# QCopterFC_MCU_Sch.net
KiCad netlist of a schematic drawn in Altium Designer
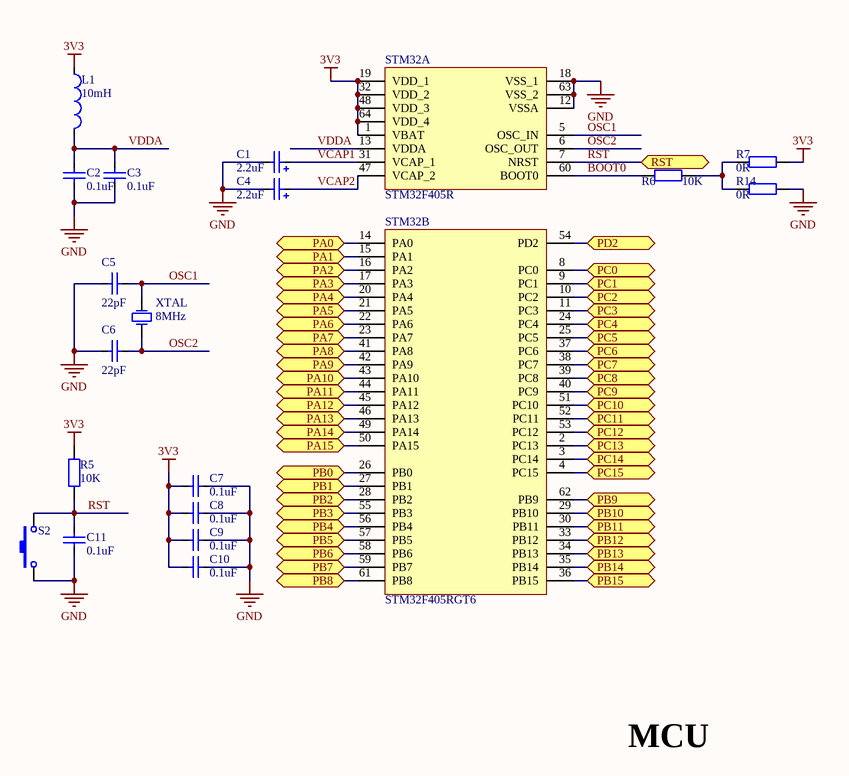
[diagram p0: QCopterFC_MCU_Sch.SchDoc]

(export (version "E")
  (design (tool "Eeschema 10.0.6"))
  (components
    (comp (ref "C1")
      (value "2.2uF")
      (footprint "PCB_Passive:CAP_TAN_P0805")
      (description "Capacitor")
      (fields (field (name "Comment") "Cap_Tan_0805"))
      (libsource (lib "SCH_Passive") (part "Cap_Tan_0805"))
    )
    (comp (ref "C2")
      (value "0.1uF")
      (footprint "PCB_Passive:CAP_0603")
      (description "Capacitor")
      (fields (field (name "Comment") "Cap_0603"))
      (libsource (lib "SCH_Passive") (part "Cap_0603"))
    )
    (comp (ref "C3")
      (value "0.1uF")
      (footprint "PCB_Passive:CAP_0603")
      (description "Capacitor")
      (fields (field (name "Comment") "Cap_0603"))
      (libsource (lib "SCH_Passive") (part "Cap_0603"))
    )
    (comp (ref "C4")
      (value "2.2uF")
      (footprint "PCB_Passive:CAP_TAN_P0805")
      (description "Capacitor")
      (fields (field (name "Comment") "Cap_Tan_0805"))
      (libsource (lib "SCH_Passive") (part "Cap_Tan_0805"))
    )
    (comp (ref "C5")
      (value "22pF")
      (footprint "PCB_Passive:CAP_0603")
      (description "Capacitor")
      (fields (field (name "Comment") "Cap_0603"))
      (libsource (lib "SCH_Passive") (part "Cap_0603"))
    )
    (comp (ref "C6")
      (value "22pF")
      (footprint "PCB_Passive:CAP_0603")
      (description "Capacitor")
      (fields (field (name "Comment") "Cap_0603"))
      (libsource (lib "SCH_Passive") (part "Cap_0603"))
    )
    (comp (ref "C7")
      (value "0.1uF")
      (footprint "PCB_Passive:CAP_0603")
      (description "Capacitor")
      (fields (field (name "Comment") "Cap_0603"))
      (libsource (lib "SCH_Passive") (part "Cap_0603"))
    )
    (comp (ref "C8")
      (value "0.1uF")
      (footprint "PCB_Passive:CAP_0603")
      (description "Capacitor")
      (fields (field (name "Comment") "Cap_0603"))
      (libsource (lib "SCH_Passive") (part "Cap_0603"))
    )
    (comp (ref "C9")
      (value "0.1uF")
      (footprint "PCB_Passive:CAP_0603")
      (description "Capacitor")
      (fields (field (name "Comment") "Cap_0603"))
      (libsource (lib "SCH_Passive") (part "Cap_0603"))
    )
    (comp (ref "C10")
      (value "0.1uF")
      (footprint "PCB_Passive:CAP_0603")
      (description "Capacitor")
      (fields (field (name "Comment") "Cap_0603"))
      (libsource (lib "SCH_Passive") (part "Cap_0603"))
    )
    (comp (ref "C11")
      (value "0.1uF")
      (footprint "PCB_Passive:CAP_0603")
      (description "Capacitor")
      (fields (field (name "Comment") "Cap_0603"))
      (libsource (lib "SCH_Passive") (part "Cap_0603"))
    )
    (comp (ref "L1")
      (value "10mH")
      (footprint "PCB_Passive:IND_0603")
      (description "Inductor")
      (fields (field (name "Comment") "Ind_0603"))
      (libsource (lib "SCH_Passive") (part "Ind_0603"))
    )
    (comp (ref "R5")
      (value "10K")
      (footprint "PCB_Passive:RES_0603")
      (description "Resistor")
      (fields (field (name "Comment") "Res_0603"))
      (libsource (lib "") (part "Res_0603_1"))
    )
    (comp (ref "R6")
      (value "10K")
      (footprint "PCB_Passive:RES_0603")
      (description "Resistor")
      (fields (field (name "Comment") "Res_0603"))
      (libsource (lib "SCH_Passive") (part "Res_0603"))
    )
    (comp (ref "R7")
      (value "0R")
      (footprint "PCB_Passive:RES_0603")
      (description "Resistor")
      (fields (field (name "Comment") "Res_0603"))
      (libsource (lib "SCH_Passive") (part "Res_0603"))
    )
    (comp (ref "R14")
      (value "0R")
      (footprint "PCB_Passive:RES_0603")
      (description "Resistor")
      (fields (field (name "Comment") "Res_0603"))
      (libsource (lib "SCH_Passive") (part "Res_0603"))
    )
    (comp (ref "S2")
      (value "SW-PB_1")
      (footprint "PCB_Switch:BT_90_T")
      (description "Switch")
      (fields (field (name "PUBLISHER") "Altium Limited"))
      (libsource (lib "SCH_Switch") (part "SW-PB_1"))
    )
    (comp (ref "STM32")
      (value "STM32F405R")
      (footprint "PCB_IC:STM32F_64")
      (description "MCU")
      (libsource (lib "SCH_IC") (part "STM32F405R"))
    )
    (comp (ref "XTAL")
      (value "8MHz")
      (footprint "PCB_Oscillator:XTAL_5032")
      (description "Crystal Oscillator")
      (fields (field (name "Comment") "XTAL_5032") (field (name "PUBLISHER") "Altium Limited"))
      (libsource (lib "SCH_Oscillator") (part "XTAL_5032"))
    )
  )
  (nets
    (net (code "1") (name "/BOOT0") (class "Default")
      (node (ref "R6") (pin "1") (pinfunction "1_1") (pintype "passive"))
      (node (ref "STM32") (pin "60") (pinfunction "BOOT0_60") (pintype "passive"))
    )
    (net (code "2") (name "/OSC1") (class "Default")
      (node (ref "C5") (pin "2") (pinfunction "2_2") (pintype "passive"))
      (node (ref "STM32") (pin "5") (pinfunction "OSC_IN_5") (pintype "passive"))
      (node (ref "XTAL") (pin "2") (pinfunction "OSC2_2") (pintype "passive"))
    )
    (net (code "3") (name "/OSC2") (class "Default")
      (node (ref "C6") (pin "2") (pinfunction "2_2") (pintype "passive"))
      (node (ref "STM32") (pin "6") (pinfunction "OSC_OUT_6") (pintype "passive"))
      (node (ref "XTAL") (pin "1") (pinfunction "OSC1_1") (pintype "passive"))
    )
    (net (code "4") (name "/PA0") (class "Default")
      (node (ref "STM32") (pin "14") (pinfunction "PA0_14") (pintype "passive"))
    )
    (net (code "5") (name "/PA1") (class "Default")
      (node (ref "STM32") (pin "15") (pinfunction "PA1_15") (pintype "passive"))
    )
    (net (code "6") (name "/PA2") (class "Default")
      (node (ref "STM32") (pin "16") (pinfunction "PA2_16") (pintype "passive"))
    )
    (net (code "7") (name "/PA3") (class "Default")
      (node (ref "STM32") (pin "17") (pinfunction "PA3_17") (pintype "passive"))
    )
    (net (code "8") (name "/PA4") (class "Default")
      (node (ref "STM32") (pin "20") (pinfunction "PA4_20") (pintype "passive"))
    )
    (net (code "9") (name "/PA5") (class "Default")
      (node (ref "STM32") (pin "21") (pinfunction "PA5_21") (pintype "passive"))
    )
    (net (code "10") (name "/PA6") (class "Default")
      (node (ref "STM32") (pin "22") (pinfunction "PA6_22") (pintype "passive"))
    )
    (net (code "11") (name "/PA7") (class "Default")
      (node (ref "STM32") (pin "23") (pinfunction "PA7_23") (pintype "passive"))
    )
    (net (code "12") (name "/PA8") (class "Default")
      (node (ref "STM32") (pin "41") (pinfunction "PA8_41") (pintype "passive"))
    )
    (net (code "13") (name "/PA9") (class "Default")
      (node (ref "STM32") (pin "42") (pinfunction "PA9_42") (pintype "passive"))
    )
    (net (code "14") (name "/PA10") (class "Default")
      (node (ref "STM32") (pin "43") (pinfunction "PA10_43") (pintype "passive"))
    )
    (net (code "15") (name "/PA11") (class "Default")
      (node (ref "STM32") (pin "44") (pinfunction "PA11_44") (pintype "passive"))
    )
    (net (code "16") (name "/PA12") (class "Default")
      (node (ref "STM32") (pin "45") (pinfunction "PA12_45") (pintype "passive"))
    )
    (net (code "17") (name "/PA13") (class "Default")
      (node (ref "STM32") (pin "46") (pinfunction "PA13_46") (pintype "passive"))
    )
    (net (code "18") (name "/PA14") (class "Default")
      (node (ref "STM32") (pin "49") (pinfunction "PA14_49") (pintype "passive"))
    )
    (net (code "19") (name "/PA15") (class "Default")
      (node (ref "STM32") (pin "50") (pinfunction "PA15_50") (pintype "passive"))
    )
    (net (code "20") (name "/PB0") (class "Default")
      (node (ref "STM32") (pin "26") (pinfunction "PB0_26") (pintype "passive"))
    )
    (net (code "21") (name "/PB1") (class "Default")
      (node (ref "STM32") (pin "27") (pinfunction "PB1_27") (pintype "passive"))
    )
    (net (code "22") (name "/PB2") (class "Default")
      (node (ref "STM32") (pin "28") (pinfunction "PB2_28") (pintype "passive"))
    )
    (net (code "23") (name "/PB3") (class "Default")
      (node (ref "STM32") (pin "55") (pinfunction "PB3_55") (pintype "passive"))
    )
    (net (code "24") (name "/PB4") (class "Default")
      (node (ref "STM32") (pin "56") (pinfunction "PB4_56") (pintype "passive"))
    )
    (net (code "25") (name "/PB5") (class "Default")
      (node (ref "STM32") (pin "57") (pinfunction "PB5_57") (pintype "passive"))
    )
    (net (code "26") (name "/PB6") (class "Default")
      (node (ref "STM32") (pin "58") (pinfunction "PB6_58") (pintype "passive"))
    )
    (net (code "27") (name "/PB7") (class "Default")
      (node (ref "STM32") (pin "59") (pinfunction "PB7_59") (pintype "passive"))
    )
    (net (code "28") (name "/PB8") (class "Default")
      (node (ref "STM32") (pin "61") (pinfunction "PB8_61") (pintype "passive"))
    )
    (net (code "29") (name "/PB9") (class "Default")
      (node (ref "STM32") (pin "62") (pinfunction "PB9_62") (pintype "passive"))
    )
    (net (code "30") (name "/PB10") (class "Default")
      (node (ref "STM32") (pin "29") (pinfunction "PB10_29") (pintype "passive"))
    )
    (net (code "31") (name "/PB11") (class "Default")
      (node (ref "STM32") (pin "30") (pinfunction "PB11_30") (pintype "passive"))
    )
    (net (code "32") (name "/PB12") (class "Default")
      (node (ref "STM32") (pin "33") (pinfunction "PB12_33") (pintype "passive"))
    )
    (net (code "33") (name "/PB13") (class "Default")
      (node (ref "STM32") (pin "34") (pinfunction "PB13_34") (pintype "passive"))
    )
    (net (code "34") (name "/PB14") (class "Default")
      (node (ref "STM32") (pin "35") (pinfunction "PB14_35") (pintype "passive"))
    )
    (net (code "35") (name "/PB15") (class "Default")
      (node (ref "STM32") (pin "36") (pinfunction "PB15_36") (pintype "passive"))
    )
    (net (code "36") (name "/PC0") (class "Default")
      (node (ref "STM32") (pin "8") (pinfunction "PC0_8") (pintype "passive"))
    )
    (net (code "37") (name "/PC1") (class "Default")
      (node (ref "STM32") (pin "9") (pinfunction "PC1_9") (pintype "passive"))
    )
    (net (code "38") (name "/PC2") (class "Default")
      (node (ref "STM32") (pin "10") (pinfunction "PC2_10") (pintype "passive"))
    )
    (net (code "39") (name "/PC3") (class "Default")
      (node (ref "STM32") (pin "11") (pinfunction "PC3_11") (pintype "passive"))
    )
    (net (code "40") (name "/PC4") (class "Default")
      (node (ref "STM32") (pin "24") (pinfunction "PC4_24") (pintype "passive"))
    )
    (net (code "41") (name "/PC5") (class "Default")
      (node (ref "STM32") (pin "25") (pinfunction "PC5_25") (pintype "passive"))
    )
    (net (code "42") (name "/PC6") (class "Default")
      (node (ref "STM32") (pin "37") (pinfunction "PC6_37") (pintype "passive"))
    )
    (net (code "43") (name "/PC7") (class "Default")
      (node (ref "STM32") (pin "38") (pinfunction "PC7_38") (pintype "passive"))
    )
    (net (code "44") (name "/PC8") (class "Default")
      (node (ref "STM32") (pin "39") (pinfunction "PC8_39") (pintype "passive"))
    )
    (net (code "45") (name "/PC9") (class "Default")
      (node (ref "STM32") (pin "40") (pinfunction "PC9_40") (pintype "passive"))
    )
    (net (code "46") (name "/PC10") (class "Default")
      (node (ref "STM32") (pin "51") (pinfunction "PC10_51") (pintype "passive"))
    )
    (net (code "47") (name "/PC11") (class "Default")
      (node (ref "STM32") (pin "52") (pinfunction "PC11_52") (pintype "passive"))
    )
    (net (code "48") (name "/PC12") (class "Default")
      (node (ref "STM32") (pin "53") (pinfunction "PC12_53") (pintype "passive"))
    )
    (net (code "49") (name "/PC13") (class "Default")
      (node (ref "STM32") (pin "2") (pinfunction "PC13_2") (pintype "passive"))
    )
    (net (code "50") (name "/PC14") (class "Default")
      (node (ref "STM32") (pin "3") (pinfunction "PC14_3") (pintype "passive"))
    )
    (net (code "51") (name "/PC15") (class "Default")
      (node (ref "STM32") (pin "4") (pinfunction "PC15_4") (pintype "passive"))
    )
    (net (code "52") (name "/PD2") (class "Default")
      (node (ref "STM32") (pin "54") (pinfunction "PD2_54") (pintype "passive"))
    )
    (net (code "53") (name "/RST") (class "Default")
      (node (ref "C11") (pin "1") (pinfunction "1_1") (pintype "passive"))
      (node (ref "R5") (pin "2") (pinfunction "2_2") (pintype "passive"))
      (node (ref "S2") (pin "2") (pinfunction "2_2") (pintype "passive"))
      (node (ref "STM32") (pin "7") (pinfunction "NRST_7") (pintype "passive"))
    )
    (net (code "54") (name "/VCAP1") (class "Default")
      (node (ref "C1") (pin "1") (pinfunction "1_1") (pintype "passive"))
      (node (ref "STM32") (pin "31") (pinfunction "VCAP_1_31") (pintype "passive"))
    )
    (net (code "55") (name "/VCAP2") (class "Default")
      (node (ref "C4") (pin "1") (pinfunction "1_1") (pintype "passive"))
      (node (ref "STM32") (pin "47") (pinfunction "VCAP_2_47") (pintype "passive"))
    )
    (net (code "56") (name "/VDDA") (class "Default")
      (node (ref "C2") (pin "1") (pinfunction "1_1") (pintype "passive"))
      (node (ref "C3") (pin "1") (pinfunction "1_1") (pintype "passive"))
      (node (ref "L1") (pin "2") (pinfunction "2_2") (pintype "passive"))
      (node (ref "STM32") (pin "13") (pinfunction "VDDA_13") (pintype "passive"))
    )
    (net (code "57") (name "3V3") (class "Default")
      (node (ref "C10") (pin "2") (pinfunction "2_2") (pintype "passive"))
      (node (ref "C7") (pin "2") (pinfunction "2_2") (pintype "passive"))
      (node (ref "C8") (pin "2") (pinfunction "2_2") (pintype "passive"))
      (node (ref "C9") (pin "2") (pinfunction "2_2") (pintype "passive"))
      (node (ref "L1") (pin "1") (pinfunction "1_1") (pintype "passive"))
      (node (ref "R5") (pin "1") (pinfunction "1_1") (pintype "passive"))
      (node (ref "R7") (pin "2") (pinfunction "2_2") (pintype "passive"))
      (node (ref "STM32") (pin "1") (pinfunction "VBAT_1") (pintype "passive"))
      (node (ref "STM32") (pin "19") (pinfunction "VDD_1_19") (pintype "passive"))
      (node (ref "STM32") (pin "32") (pinfunction "VDD_2_32") (pintype "passive"))
      (node (ref "STM32") (pin "48") (pinfunction "VDD_3_48") (pintype "passive"))
      (node (ref "STM32") (pin "64") (pinfunction "VDD_4_64") (pintype "passive"))
    )
    (net (code "58") (name "GND") (class "Default")
      (node (ref "C1") (pin "2") (pinfunction "2_2") (pintype "passive"))
      (node (ref "C10") (pin "1") (pinfunction "1_1") (pintype "passive"))
      (node (ref "C11") (pin "2") (pinfunction "2_2") (pintype "passive"))
      (node (ref "C2") (pin "2") (pinfunction "2_2") (pintype "passive"))
      (node (ref "C3") (pin "2") (pinfunction "2_2") (pintype "passive"))
      (node (ref "C4") (pin "2") (pinfunction "2_2") (pintype "passive"))
      (node (ref "C5") (pin "1") (pinfunction "1_1") (pintype "passive"))
      (node (ref "C6") (pin "1") (pinfunction "1_1") (pintype "passive"))
      (node (ref "C7") (pin "1") (pinfunction "1_1") (pintype "passive"))
      (node (ref "C8") (pin "1") (pinfunction "1_1") (pintype "passive"))
      (node (ref "C9") (pin "1") (pinfunction "1_1") (pintype "passive"))
      (node (ref "R14") (pin "2") (pinfunction "2_2") (pintype "passive"))
      (node (ref "S2") (pin "1") (pinfunction "1_1") (pintype "passive"))
      (node (ref "STM32") (pin "12") (pinfunction "VSSA_12") (pintype "passive"))
      (node (ref "STM32") (pin "18") (pinfunction "VSS_1_18") (pintype "passive"))
      (node (ref "STM32") (pin "63") (pinfunction "VSS_2_63") (pintype "passive"))
    )
    (net (code "59") (name "Net-(R14-Pad1)") (class "Default")
      (node (ref "R14") (pin "1") (pinfunction "1_1") (pintype "passive"))
      (node (ref "R6") (pin "2") (pinfunction "2_2") (pintype "passive"))
      (node (ref "R7") (pin "1") (pinfunction "1_1") (pintype "passive"))
    )
  )
)
